# FAN__Digital_Dimmer.net
KiCad netlist of a schematic drawn in EasyEDA
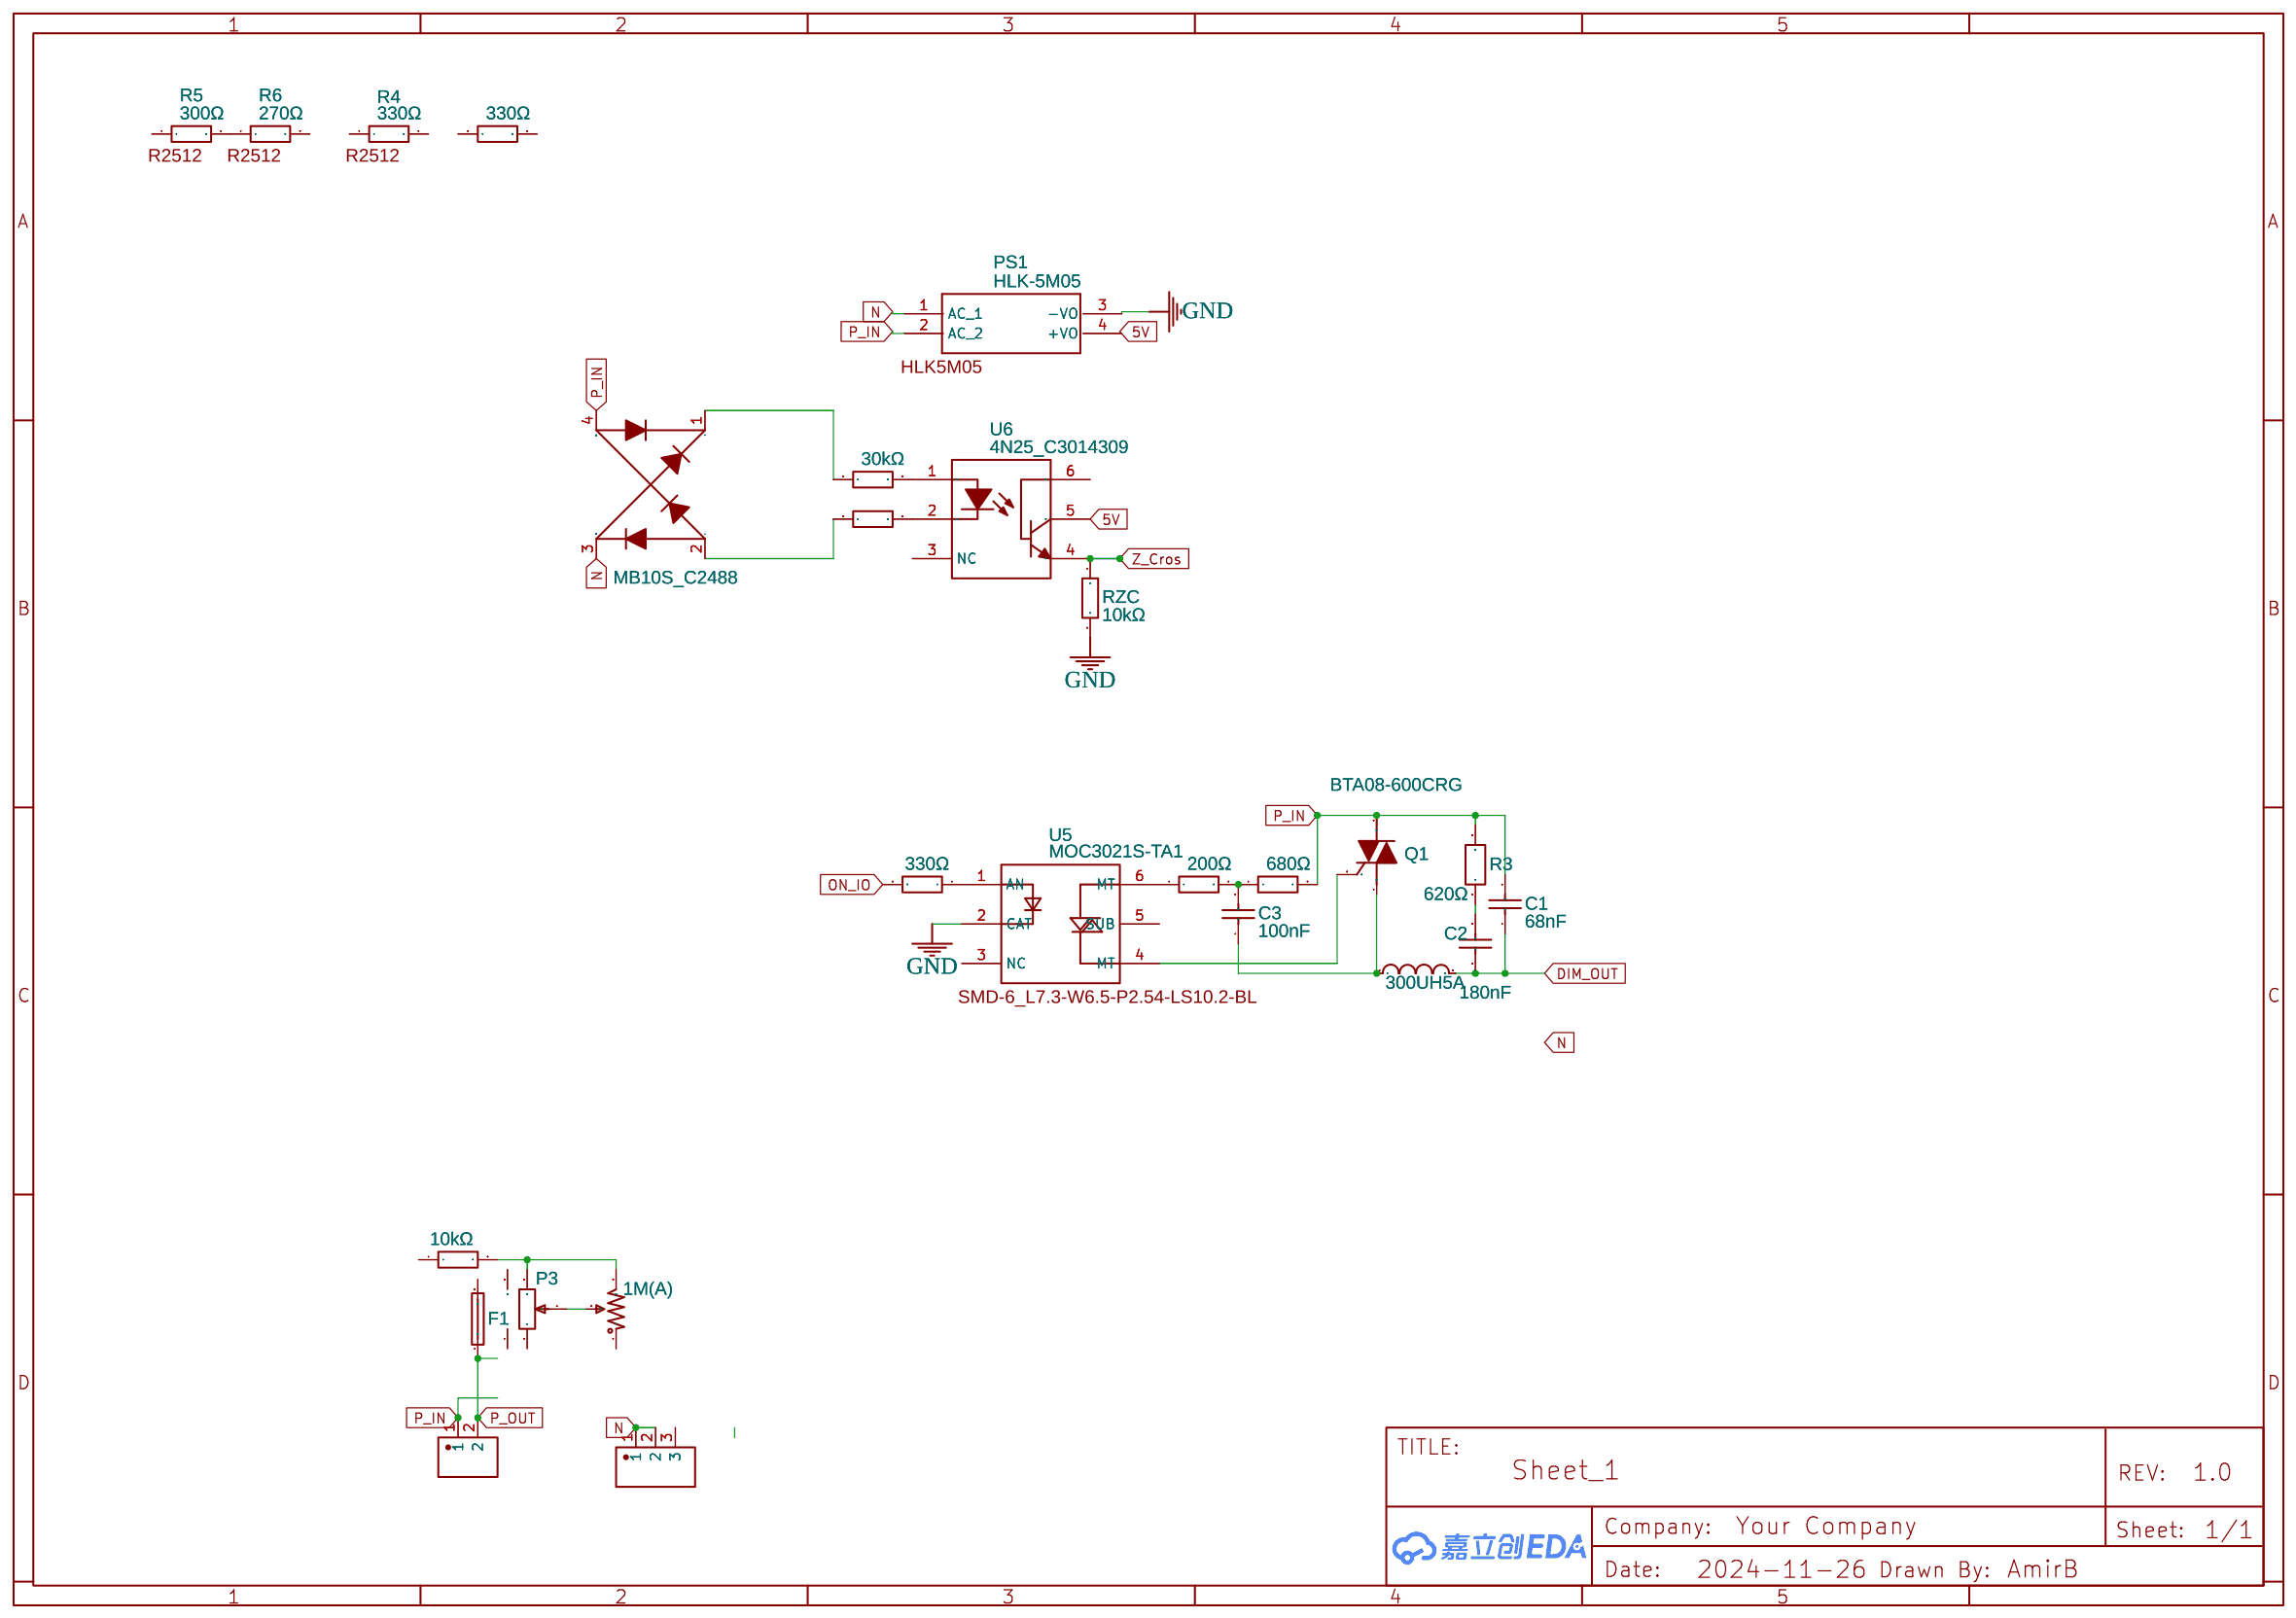
[diagram p0: schematic sheet]

(export (version "E")
  (design (tool "Eeschema 10.0.6"))
  (components
    (comp (ref "C1")
      (value "68nF")
      (fields
        (field (name "Manufacturer Part") "MPP683J2G1305095LC")
        (field (name "Manufacturer") "SRD(圣融达)")
      )
      (libsource (lib "") (part "MPP683J4130509LC"))
    )
    (comp (ref "C2")
      (value "180nF")
      (fields
        (field (name "Manufacturer Part") "MPP184J2G1306106LC")
        (field (name "Manufacturer") "SRD(圣融达)")
      )
      (libsource (lib "") (part "MPP184J4130610LC"))
    )
    (comp (ref "C3")
      (value "100nF")
      (fields (field (name "Manufacturer Part") "MP2104K27C3R6LC") (field (name "Manufacturer") "SRD(圣融达)"))
      (libsource (lib "") (part "MP2104KGC3RLC"))
    )
    (comp (ref "D1")
      (value "MB10S_C2488")
      (fields (field (name "Manufacturer Part") "MB10S") (field (name "Manufacturer") "MDD(辰达半导体)"))
      (libsource (lib "") (part "MB10S_C2488"))
    )
    (comp (ref "F1")
      (value "0215002.MXEP")
      (fields (field (name "Manufacturer") "Littelfuse(美国力特)"))
      (libsource (lib "") (part "0215002.MXEP"))
    )
    (comp (ref "P3")
      (value "长柄旋转电位器")
      (fields (field (name "BOM_Supplier Part") "C2874842"))
      (libsource (lib "") (part "长柄旋转电位器"))
    )
    (comp (ref "P7")
      (value "1M(A)")
      (fields (field (name "Manufacturer Part") "3296W-1-103") (field (name "Manufacturer") "BOCHEN(博晨)"))
      (libsource (lib "") (part "3296W-1-103"))
    )
    (comp (ref "PS1") (value "HLK-5M05") (libsource (lib "") (part "HLK-5M05")))
    (comp (ref "Q1")
      (value "BTA08-600CRG")
      (fields (field (name "Manufacturer") "ST(意法半导体)"))
      (libsource (lib "") (part "BTA08-600CRG"))
    )
    (comp (ref "R1")
      (value "30kΩ")
      (fields
        (field (name "Manufacturer Part") "25121WJ0303T4E")
        (field (name "Manufacturer") "UNI-ROYAL(厚声)")
      )
      (libsource (lib "") (part "25121WJ0303T4E"))
    )
    (comp (ref "R2")
      (value "30kΩ")
      (fields
        (field (name "Manufacturer Part") "25121WJ0303T4E")
        (field (name "Manufacturer") "UNI-ROYAL(厚声)")
      )
      (libsource (lib "") (part "25121WJ0303T4E"))
    )
    (comp (ref "R3")
      (value "620Ω")
      (fields
        (field (name "Manufacturer Part") "25121WJ0621T4E")
        (field (name "Manufacturer") "UNI-ROYAL(厚声)")
      )
      (libsource (lib "") (part "25121WJ0621T4E"))
    )
    (comp (ref "R4")
      (value "330Ω")
      (fields
        (field (name "Manufacturer Part") "25121WJ0331T4E")
        (field (name "Manufacturer") "UNI-ROYAL(厚声)")
      )
      (libsource (lib "") (part "25121WJ0331T4E_1"))
    )
    (comp (ref "R5")
      (value "300Ω")
      (fields
        (field (name "Manufacturer Part") "25121WJ0301T4E")
        (field (name "Manufacturer") "UNI-ROYAL(厚声)")
      )
      (libsource (lib "") (part "25121WJ0301T4E"))
    )
    (comp (ref "R6")
      (value "270Ω")
      (fields
        (field (name "Manufacturer Part") "25121WJ0271T4E")
        (field (name "Manufacturer") "UNI-ROYAL(厚声)")
      )
      (libsource (lib "") (part "25121WJ0271T4E"))
    )
    (comp (ref "R7")
      (value "330Ω")
      (fields
        (field (name "Manufacturer Part") "25121WJ0331T4E")
        (field (name "Manufacturer") "UNI-ROYAL(厚声)")
      )
      (libsource (lib "") (part "25121WJ0331T4E"))
    )
    (comp (ref "R8")
      (value "200Ω")
      (fields
        (field (name "Manufacturer Part") "25121WJ0201T4E")
        (field (name "Manufacturer") "UNI-ROYAL(厚声)")
      )
      (libsource (lib "") (part "25121WJ0201T4E"))
    )
    (comp (ref "R9")
      (value "680Ω")
      (fields
        (field (name "Manufacturer Part") "25121WJ0681T4E")
        (field (name "Manufacturer") "UNI-ROYAL(厚声)")
      )
      (libsource (lib "") (part "25121WJ0681T4E"))
    )
    (comp (ref "R14")
      (value "330Ω")
      (fields
        (field (name "Manufacturer Part") "0603WAF3300T5E")
        (field (name "Manufacturer") "UNI-ROYAL(厚声)")
      )
      (libsource (lib "") (part "0603WAF3300T5E"))
    )
    (comp (ref "RL1V")
      (value "10kΩ")
      (fields
        (field (name "BOM_Manufacturer Part") "0603WAF1002T5E")
        (field (name "BOM_Supplier Part") "C25804")
      )
      (libsource (lib "") (part "0603WAF1002T5E_1"))
    )
    (comp (ref "RZC")
      (value "10kΩ")
      (fields
        (field (name "BOM_Manufacturer Part") "0603WAF1002T5E")
        (field (name "BOM_Supplier Part") "C25804")
      )
      (libsource (lib "") (part "0603WAF1002T5E"))
    )
    (comp (ref "U1")
      (value "KF301R-5.0-3P")
      (fields (field (name "Manufacturer") "KEFA(科发)"))
      (libsource (lib "") (part "KF301R-5.0-3P"))
    )
    (comp (ref "U2")
      (value "KF301-5.0-2P")
      (fields (field (name "Manufacturer") "KEFA(科发)"))
      (libsource (lib "") (part "KF301-5.0-2P"))
    )
    (comp (ref "U3") (value "300UH5A") (libsource (lib "") (part "300UH5A")))
    (comp (ref "U5")
      (value "MOC3021S-TA1")
      (fields (field (name "Manufacturer") "LITEON(光宝)"))
      (libsource (lib "") (part "MOC3021S-TA1"))
    )
    (comp (ref "U6")
      (value "4N25_C3014309")
      (fields (field (name "Manufacturer Part") "4N25") (field (name "Manufacturer") "UMW(友台半导体)"))
      (libsource (lib "") (part "4N25_C3014309"))
    )
  )
  (nets
    (net (code "1") (name "5V") (class "Default")
      (node (ref "U6") (pin "5") (pinfunction "5_5") (pintype "unspecified"))
    )
    (net (code "2") (name "DIM_OUT") (class "Default")
      (node (ref "C1") (pin "1") (pinfunction "1_1") (pintype "input"))
      (node (ref "C2") (pin "1") (pinfunction "1_1") (pintype "input"))
      (node (ref "U3") (pin "2") (pinfunction "2_2") (pintype "unspecified"))
    )
    (net (code "3") (name "GND") (class "Default")
      (node (ref "PS1") (pin "3") (pinfunction "-VO_3") (pintype "bidirectional"))
      (node (ref "RZC") (pin "2") (pinfunction "2_2") (pintype "input"))
      (node (ref "U5") (pin "2") (pinfunction "CAT_2") (pintype "unspecified"))
    )
    (net (code "4") (name "N") (class "Default")
      (node (ref "D1") (pin "3") (pinfunction "C2_3") (pintype "unspecified"))
      (node (ref "PS1") (pin "1") (pinfunction "AC_1_1") (pintype "bidirectional"))
      (node (ref "U1") (pin "1") (pinfunction "1_1") (pintype "unspecified"))
      (node (ref "U1") (pin "2") (pinfunction "2_2") (pintype "unspecified"))
    )
    (net (code "5") (name "Net-(C2-Pad2)") (class "Default")
      (node (ref "C2") (pin "2") (pinfunction "2_2") (pintype "input"))
      (node (ref "R3") (pin "1") (pinfunction "1_1") (pintype "unspecified"))
    )
    (net (code "6") (name "Net-(C3-Pad2)") (class "Default")
      (node (ref "C3") (pin "2") (pinfunction "2_2") (pintype "input"))
      (node (ref "R8") (pin "2") (pinfunction "2_2") (pintype "input"))
      (node (ref "R9") (pin "1") (pinfunction "1_1") (pintype "unspecified"))
    )
    (net (code "7") (name "Net-(D1-+)") (class "Default")
      (node (ref "D1") (pin "1") (pinfunction "+_1") (pintype "unspecified"))
      (node (ref "R1") (pin "1") (pinfunction "1_1") (pintype "input"))
    )
    (net (code "8") (name "Net-(D1--)") (class "Default")
      (node (ref "D1") (pin "2") (pinfunction "-_2") (pintype "unspecified"))
      (node (ref "R2") (pin "1") (pinfunction "1_1") (pintype "input"))
    )
    (net (code "9") (name "Net-(P3-Pad2)") (class "Default")
      (node (ref "P3") (pin "2") (pinfunction "2_2") (pintype "input"))
      (node (ref "P7") (pin "2") (pinfunction "2_2") (pintype "unspecified"))
    )
    (net (code "10") (name "Net-(P3-Pad3)") (class "Default")
      (node (ref "P3") (pin "3") (pinfunction "3_3") (pintype "input"))
      (node (ref "P7") (pin "3") (pinfunction "3_3") (pintype "unspecified"))
      (node (ref "RL1V") (pin "2") (pinfunction "2_2") (pintype "input"))
    )
    (net (code "11") (name "Net-(Q1-G)") (class "Default")
      (node (ref "Q1") (pin "3") (pinfunction "G_3") (pintype "unspecified"))
      (node (ref "U5") (pin "4") (pinfunction "MT_4") (pintype "unspecified"))
    )
    (net (code "12") (name "Net-(Q1-M1)") (class "Default")
      (node (ref "C3") (pin "1") (pinfunction "1_1") (pintype "input"))
      (node (ref "Q1") (pin "1") (pinfunction "M1_1") (pintype "unspecified"))
      (node (ref "U3") (pin "1") (pinfunction "1_1") (pintype "unspecified"))
    )
    (net (code "13") (name "Net-(R1-Pad2)") (class "Default")
      (node (ref "R1") (pin "2") (pinfunction "2_2") (pintype "input"))
      (node (ref "U6") (pin "1") (pinfunction "1_1") (pintype "unspecified"))
    )
    (net (code "14") (name "Net-(R2-Pad2)") (class "Default")
      (node (ref "R2") (pin "2") (pinfunction "2_2") (pintype "input"))
      (node (ref "U6") (pin "2") (pinfunction "2_2") (pintype "unspecified"))
    )
    (net (code "15") (name "Net-(R5-Pad2)") (class "Default")
      (node (ref "R5") (pin "2") (pinfunction "2_2") (pintype "input"))
      (node (ref "R6") (pin "1") (pinfunction "1_1") (pintype "input"))
    )
    (net (code "16") (name "Net-(R8-Pad1)") (class "Default")
      (node (ref "R8") (pin "1") (pinfunction "1_1") (pintype "input"))
      (node (ref "U5") (pin "6") (pinfunction "MT_6") (pintype "unspecified"))
    )
    (net (code "17") (name "Net-(U5-AN)") (class "Default")
      (node (ref "R14") (pin "1") (pinfunction "1_1") (pintype "input"))
      (node (ref "U5") (pin "1") (pinfunction "AN_1") (pintype "unspecified"))
    )
    (net (code "18") (name "ON_IO") (class "Default")
      (node (ref "R14") (pin "2") (pinfunction "2_2") (pintype "input"))
    )
    (net (code "19") (name "P_IN") (class "Default")
      (node (ref "C1") (pin "2") (pinfunction "2_2") (pintype "input"))
      (node (ref "D1") (pin "4") (pinfunction "C1_4") (pintype "unspecified"))
      (node (ref "PS1") (pin "2") (pinfunction "AC_2_2") (pintype "bidirectional"))
      (node (ref "Q1") (pin "2") (pinfunction "M2_2") (pintype "unspecified"))
      (node (ref "R3") (pin "2") (pinfunction "2_2") (pintype "unspecified"))
      (node (ref "R9") (pin "2") (pinfunction "2_2") (pintype "unspecified"))
      (node (ref "U2") (pin "1") (pinfunction "1_1") (pintype "unspecified"))
    )
    (net (code "20") (name "P_OUT") (class "Default")
      (node (ref "F1") (pin "1") (pinfunction "1_1") (pintype "unspecified"))
      (node (ref "U2") (pin "2") (pinfunction "2_2") (pintype "unspecified"))
    )
    (net (code "21") (name "Z_Cros") (class "Default")
      (node (ref "RZC") (pin "1") (pinfunction "1_1") (pintype "input"))
      (node (ref "U6") (pin "4") (pinfunction "4_4") (pintype "unspecified"))
    )
    (net (code "22") (name "unconnected-(F1-Pad2)") (class "Default")
      (node (ref "F1") (pin "2") (pinfunction "2_2") (pintype "unspecified"))
    )
    (net (code "23") (name "unconnected-(P3-Pad1)") (class "Default")
      (node (ref "P3") (pin "1") (pinfunction "1_1") (pintype "input"))
    )
    (net (code "24") (name "unconnected-(P3-Pad4)") (class "Default")
      (node (ref "P3") (pin "4") (pinfunction "4_4") (pintype "input"))
    )
    (net (code "25") (name "unconnected-(P3-Pad5)") (class "Default")
      (node (ref "P3") (pin "5") (pinfunction "5_5") (pintype "input"))
    )
    (net (code "26") (name "unconnected-(P7-Pad1)") (class "Default")
      (node (ref "P7") (pin "1") (pinfunction "1_1") (pintype "unspecified"))
    )
    (net (code "27") (name "unconnected-(PS1-+VO-Pad4)") (class "Default")
      (node (ref "PS1") (pin "4") (pinfunction "+VO_4") (pintype "bidirectional"))
    )
    (net (code "28") (name "unconnected-(R4-Pad1)") (class "Default")
      (node (ref "R4") (pin "1") (pinfunction "1_1") (pintype "input"))
    )
    (net (code "29") (name "unconnected-(R4-Pad2)") (class "Default")
      (node (ref "R4") (pin "2") (pinfunction "2_2") (pintype "input"))
    )
    (net (code "30") (name "unconnected-(R5-Pad1)") (class "Default")
      (node (ref "R5") (pin "1") (pinfunction "1_1") (pintype "input"))
    )
    (net (code "31") (name "unconnected-(R6-Pad2)") (class "Default")
      (node (ref "R6") (pin "2") (pinfunction "2_2") (pintype "input"))
    )
    (net (code "32") (name "unconnected-(R7-Pad1)") (class "Default")
      (node (ref "R7") (pin "1") (pinfunction "1_1") (pintype "input"))
    )
    (net (code "33") (name "unconnected-(R7-Pad2)") (class "Default")
      (node (ref "R7") (pin "2") (pinfunction "2_2") (pintype "input"))
    )
    (net (code "34") (name "unconnected-(RL1V-Pad1)") (class "Default")
      (node (ref "RL1V") (pin "1") (pinfunction "1_1") (pintype "input"))
    )
    (net (code "35") (name "unconnected-(U1-Pad3)") (class "Default")
      (node (ref "U1") (pin "3") (pinfunction "3_3") (pintype "unspecified"))
    )
    (net (code "36") (name "unconnected-(U5-NC-Pad3)") (class "Default")
      (node (ref "U5") (pin "3") (pinfunction "NC_3") (pintype "unspecified"))
    )
    (net (code "37") (name "unconnected-(U5-SUB-Pad5)") (class "Default")
      (node (ref "U5") (pin "5") (pinfunction "SUB_5") (pintype "unspecified"))
    )
    (net (code "38") (name "unconnected-(U6-NC-Pad3)") (class "Default")
      (node (ref "U6") (pin "3") (pinfunction "NC_3") (pintype "unspecified"))
    )
    (net (code "39") (name "unconnected-(U6-Pad6)") (class "Default")
      (node (ref "U6") (pin "6") (pinfunction "6_6") (pintype "unspecified"))
    )
  )
)
